# Voice.net
KiCad netlist of a schematic drawn in Altium Designer
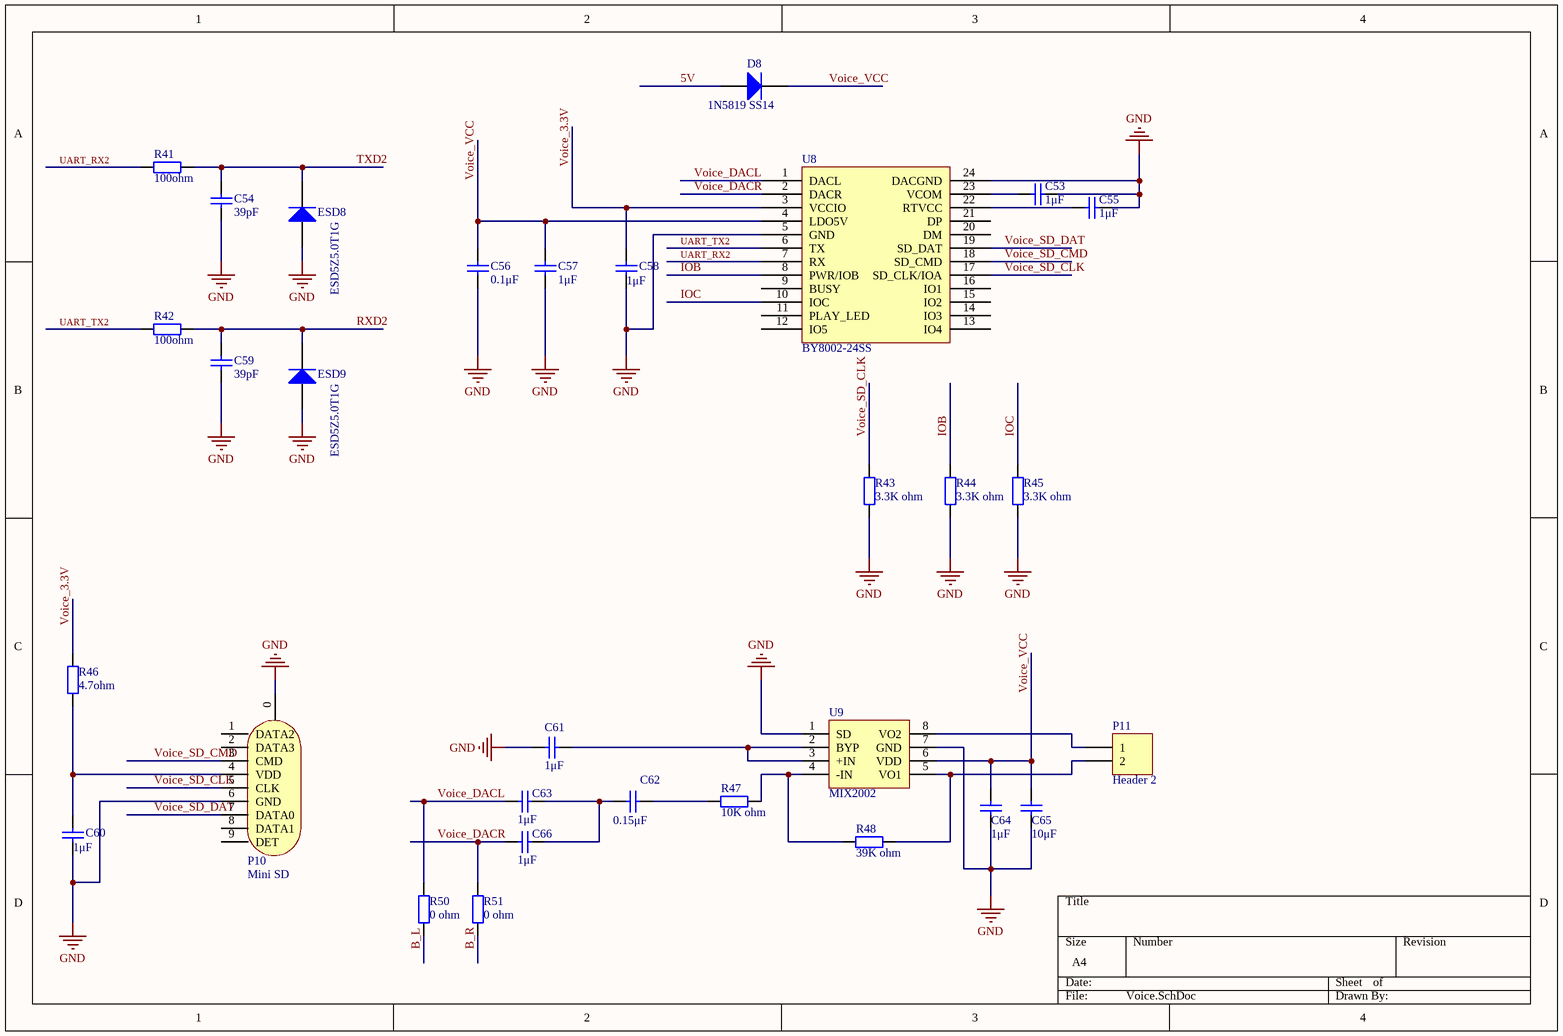
[diagram p0: Voice.SchDoc]

(export (version "E")
  (design (tool "Eeschema 10.0.6"))
  (components
    (comp (ref "C53")
      (value "1μF")
      (footprint "0603C")
      (description "1μF_50V,X5R,±10%")
      (libsource (lib "Yang_Lib") (part "Cap_1μF_50V_0603"))
    )
    (comp (ref "C54")
      (value "39pF")
      (footprint "0603C")
      (description "39pF_50V,C0G (EIA),±1%")
      (libsource (lib "Yang_Lib") (part "Cap_39pF_50V_0603"))
    )
    (comp (ref "C55")
      (value "1μF")
      (footprint "0603C")
      (description "1μF_50V,X5R,±10%")
      (libsource (lib "Yang_Lib") (part "Cap_1μF_50V_0603"))
    )
    (comp (ref "C56")
      (value "0.1μF")
      (footprint "0603C")
      (description "0.1μF_50V,X7R,±5%")
      (libsource (lib "Yang_Lib") (part "Cap_0.1μF_50V_0603"))
    )
    (comp (ref "C57")
      (value "1μF")
      (footprint "0603C")
      (description "1μF_50V,X5R,±10%")
      (libsource (lib "Yang_Lib") (part "Cap_1μF_50V_0603"))
    )
    (comp (ref "C58")
      (value "1μF")
      (footprint "0603C")
      (description "1μF_50V,X5R,±10%")
      (libsource (lib "Yang_Lib") (part "Cap_1μF_50V_0603"))
    )
    (comp (ref "C59")
      (value "39pF")
      (footprint "0603C")
      (description "39pF_50V,C0G (EIA),±1%")
      (libsource (lib "Yang_Lib") (part "Cap_39pF_50V_0603"))
    )
    (comp (ref "C60")
      (value "1μF")
      (footprint "0603C")
      (description "1μF_50V,X5R,±10%")
      (libsource (lib "Yang_Lib") (part "Cap_1μF_50V_0603"))
    )
    (comp (ref "C61")
      (value "1μF")
      (footprint "0603C")
      (description "1μF_50V,X5R,±10%")
      (libsource (lib "Yang_Lib") (part "Cap_1μF_50V_0603"))
    )
    (comp (ref "C62")
      (value "0.15μF")
      (footprint "0603C")
      (description "0.15μF_50V,X7R,±5%")
      (libsource (lib "Yang_Lib") (part "Cap_0.15μF_50V_0603"))
    )
    (comp (ref "C63")
      (value "1μF")
      (footprint "0603C")
      (description "1μF_50V,X5R,±10%")
      (libsource (lib "Yang_Lib") (part "Cap_1μF_50V_0603"))
    )
    (comp (ref "C64")
      (value "1μF")
      (footprint "0603C")
      (description "1μF_50V,X5R,±10%")
      (libsource (lib "Yang_Lib") (part "Cap_1μF_50V_0603"))
    )
    (comp (ref "C65")
      (value "10μF")
      (footprint "0603C")
      (description "10μF_35V,X5R,20%")
      (libsource (lib "Yang_Lib") (part "Cap_10μF_35V_0603"))
    )
    (comp (ref "C66")
      (value "1μF")
      (footprint "0603C")
      (description "1μF_50V,X5R,±10%")
      (libsource (lib "Yang_Lib") (part "Cap_1μF_50V_0603"))
    )
    (comp (ref "D8")
      (value "1N5819 SS14")
      (footprint "SMA-small")
      (libsource (lib "Yang_Lib") (part "1N5819 SS14_SMA"))
    )
    (comp (ref "ESD8")
      (value "ESD5Z5.0T1G")
      (footprint "SOD523")
      (libsource (lib "Yang_Lib") (part "ESD5Z5.0T1G_SOD523"))
    )
    (comp (ref "ESD9")
      (value "ESD5Z5.0T1G")
      (footprint "SOD523")
      (libsource (lib "Yang_Lib") (part "ESD5Z5.0T1G_SOD523"))
    )
    (comp (ref "P10") (value "Mini SD") (footprint "TF-tan") (libsource (lib "Yang_Lib") (part "Mini SD")))
    (comp (ref "P11")
      (value "Header 2")
      (footprint "HDR1X2")
      (description "Header, 2-Pin")
      (fields (field (name "PUBLISHER") "Altium Limited"))
      (libsource (lib "Miscellaneous Connectors") (part "Header 2"))
    )
    (comp (ref "R41")
      (value "100ohm")
      (footprint "0603R")
      (description "100 ohm_5%")
      (libsource (lib "Yang_Lib") (part "Res_100ohm_0603"))
    )
    (comp (ref "R42")
      (value "100ohm")
      (footprint "0603R")
      (description "100 ohm_5%")
      (libsource (lib "Yang_Lib") (part "Res_100ohm_0603"))
    )
    (comp (ref "R43")
      (value "3.3K ohm")
      (footprint "0603R")
      (description "3.3K ohm,1%")
      (libsource (lib "Yang_Lib") (part "Res_3.3K ohm_0603"))
    )
    (comp (ref "R44")
      (value "3.3K ohm")
      (footprint "0603R")
      (description "3.3K ohm,1%")
      (libsource (lib "Yang_Lib") (part "Res_3.3K ohm_0603"))
    )
    (comp (ref "R45")
      (value "3.3K ohm")
      (footprint "0603R")
      (description "3.3K ohm,1%")
      (libsource (lib "Yang_Lib") (part "Res_3.3K ohm_0603"))
    )
    (comp (ref "R46")
      (value "4.7ohm")
      (footprint "0603R")
      (description "4.7ohm,1%")
      (libsource (lib "Yang_Lib") (part "Res_4.7ohm_0603"))
    )
    (comp (ref "R47")
      (value "10K ohm")
      (footprint "0603R")
      (description "10K ohm,1%")
      (libsource (lib "Yang_Lib") (part "Res_10K ohm_0603"))
    )
    (comp (ref "R48")
      (value "39K ohm")
      (footprint "0603R")
      (description "39K ohm,1%")
      (libsource (lib "Yang_Lib") (part "Res_39K ohm_0603"))
    )
    (comp (ref "R50")
      (value "0 ohm")
      (footprint "0603R")
      (description "0 ohm,5%")
      (libsource (lib "Yang_Lib") (part "Res_0 ohm_0603"))
    )
    (comp (ref "R51")
      (value "0 ohm")
      (footprint "0603R")
      (description "0 ohm,5%")
      (libsource (lib "Yang_Lib") (part "Res_0 ohm_0603"))
    )
    (comp (ref "U8")
      (value "BY8002-24SS")
      (footprint "QSOP-24N")
      (libsource (lib "Yang_Lib") (part "BY8002-24SS"))
    )
    (comp (ref "U9")
      (value "MIX2002")
      (footprint "SOP8 - NO-HP")
      (libsource (lib "Yang_Lib") (part "MIX2002"))
    )
  )
  (nets
    (net (code "1") (name "/5V") (class "Default")
      (node (ref "D8") (pin "1") (pinfunction "A_1") (pintype "passive"))
    )
    (net (code "2") (name "/B_L") (class "Default")
      (node (ref "R50") (pin "1") (pinfunction "1_1") (pintype "passive"))
    )
    (net (code "3") (name "/B_R") (class "Default")
      (node (ref "R51") (pin "1") (pinfunction "1_1") (pintype "passive"))
    )
    (net (code "4") (name "/IOB") (class "Default")
      (node (ref "R44") (pin "2") (pinfunction "2_2") (pintype "passive"))
      (node (ref "U8") (pin "8") (pinfunction "PWR/IOB_8") (pintype "passive"))
    )
    (net (code "5") (name "/IOC") (class "Default")
      (node (ref "R45") (pin "2") (pinfunction "2_2") (pintype "passive"))
      (node (ref "U8") (pin "10") (pinfunction "IOC_10") (pintype "passive"))
    )
    (net (code "6") (name "/RXD2") (class "Default")
      (node (ref "C59") (pin "2") (pinfunction "2_2") (pintype "passive"))
      (node (ref "ESD9") (pin "2") (pinfunction "K_2") (pintype "passive"))
      (node (ref "R42") (pin "2") (pinfunction "2_2") (pintype "passive"))
    )
    (net (code "7") (name "/TXD2") (class "Default")
      (node (ref "C54") (pin "2") (pinfunction "2_2") (pintype "passive"))
      (node (ref "ESD8") (pin "2") (pinfunction "K_2") (pintype "passive"))
      (node (ref "R41") (pin "2") (pinfunction "2_2") (pintype "passive"))
    )
    (net (code "8") (name "/UART_RX2") (class "Default")
      (node (ref "R41") (pin "1") (pinfunction "1_1") (pintype "passive"))
      (node (ref "U8") (pin "7") (pinfunction "RX_7") (pintype "passive"))
    )
    (net (code "9") (name "/UART_TX2") (class "Default")
      (node (ref "R42") (pin "1") (pinfunction "1_1") (pintype "passive"))
      (node (ref "U8") (pin "6") (pinfunction "TX_6") (pintype "passive"))
    )
    (net (code "10") (name "/Voice_3.3V") (class "Default")
      (node (ref "C58") (pin "2") (pinfunction "2_2") (pintype "passive"))
      (node (ref "R46") (pin "2") (pinfunction "2_2") (pintype "passive"))
      (node (ref "U8") (pin "3") (pinfunction "VCCIO_3") (pintype "passive"))
    )
    (net (code "11") (name "/Voice_DACL") (class "Default")
      (node (ref "C63") (pin "1") (pinfunction "1_1") (pintype "passive"))
      (node (ref "R50") (pin "2") (pinfunction "2_2") (pintype "passive"))
      (node (ref "U8") (pin "1") (pinfunction "DACL_1") (pintype "passive"))
    )
    (net (code "12") (name "/Voice_DACR") (class "Default")
      (node (ref "C66") (pin "1") (pinfunction "1_1") (pintype "passive"))
      (node (ref "R51") (pin "2") (pinfunction "2_2") (pintype "passive"))
      (node (ref "U8") (pin "2") (pinfunction "DACR_2") (pintype "passive"))
    )
    (net (code "13") (name "/Voice_SD_CLK") (class "Default")
      (node (ref "P10") (pin "5") (pinfunction "CLK_5") (pintype "passive"))
      (node (ref "R43") (pin "2") (pinfunction "2_2") (pintype "passive"))
      (node (ref "U8") (pin "17") (pinfunction "SD_CLK/IOA_17") (pintype "passive"))
    )
    (net (code "14") (name "/Voice_SD_CMD") (class "Default")
      (node (ref "P10") (pin "3") (pinfunction "CMD_3") (pintype "passive"))
      (node (ref "U8") (pin "18") (pinfunction "SD_CMD_18") (pintype "passive"))
    )
    (net (code "15") (name "/Voice_SD_DAT") (class "Default")
      (node (ref "P10") (pin "7") (pinfunction "DATA0_7") (pintype "passive"))
      (node (ref "U8") (pin "19") (pinfunction "SD_DAT_19") (pintype "passive"))
    )
    (net (code "16") (name "/Voice_VCC") (class "Default")
      (node (ref "C56") (pin "2") (pinfunction "2_2") (pintype "passive"))
      (node (ref "C57") (pin "2") (pinfunction "2_2") (pintype "passive"))
      (node (ref "C64") (pin "2") (pinfunction "2_2") (pintype "passive"))
      (node (ref "C65") (pin "2") (pinfunction "2_2") (pintype "passive"))
      (node (ref "D8") (pin "2") (pinfunction "K_2") (pintype "passive"))
      (node (ref "U8") (pin "4") (pinfunction "LDO5V_4") (pintype "passive"))
      (node (ref "U9") (pin "6") (pinfunction "VDD_6") (pintype "passive"))
    )
    (net (code "17") (name "GND") (class "Default")
      (node (ref "C53") (pin "1") (pinfunction "1_1") (pintype "passive"))
      (node (ref "C54") (pin "1") (pinfunction "1_1") (pintype "passive"))
      (node (ref "C55") (pin "1") (pinfunction "1_1") (pintype "passive"))
      (node (ref "C56") (pin "1") (pinfunction "1_1") (pintype "passive"))
      (node (ref "C57") (pin "1") (pinfunction "1_1") (pintype "passive"))
      (node (ref "C58") (pin "1") (pinfunction "1_1") (pintype "passive"))
      (node (ref "C59") (pin "1") (pinfunction "1_1") (pintype "passive"))
      (node (ref "C60") (pin "1") (pinfunction "1_1") (pintype "passive"))
      (node (ref "C61") (pin "1") (pinfunction "1_1") (pintype "passive"))
      (node (ref "C64") (pin "1") (pinfunction "1_1") (pintype "passive"))
      (node (ref "C65") (pin "1") (pinfunction "1_1") (pintype "passive"))
      (node (ref "ESD8") (pin "1") (pinfunction "A_1") (pintype "passive"))
      (node (ref "ESD9") (pin "1") (pinfunction "A_1") (pintype "passive"))
      (node (ref "P10") (pin "0") (pinfunction "0_0") (pintype "passive"))
      (node (ref "P10") (pin "6") (pinfunction "GND_6") (pintype "passive"))
      (node (ref "R43") (pin "1") (pinfunction "1_1") (pintype "passive"))
      (node (ref "R44") (pin "1") (pinfunction "1_1") (pintype "passive"))
      (node (ref "R45") (pin "1") (pinfunction "1_1") (pintype "passive"))
      (node (ref "U8") (pin "24") (pinfunction "DACGND_24") (pintype "passive"))
      (node (ref "U8") (pin "5") (pinfunction "GND_5") (pintype "passive"))
      (node (ref "U9") (pin "1") (pinfunction "SD_1") (pintype "passive"))
      (node (ref "U9") (pin "7") (pinfunction "GND_7") (pintype "passive"))
    )
    (net (code "18") (name "Net-(C62-Pad1)") (class "Default")
      (node (ref "C62") (pin "1") (pinfunction "1_1") (pintype "passive"))
      (node (ref "C63") (pin "2") (pinfunction "2_2") (pintype "passive"))
      (node (ref "C66") (pin "2") (pinfunction "2_2") (pintype "passive"))
    )
    (net (code "19") (name "Net-(C62-Pad2)") (class "Default")
      (node (ref "C62") (pin "2") (pinfunction "2_2") (pintype "passive"))
      (node (ref "R47") (pin "1") (pinfunction "1_1") (pintype "passive"))
    )
    (net (code "20") (name "Net-(P10-VDD)") (class "Default")
      (node (ref "C60") (pin "2") (pinfunction "2_2") (pintype "passive"))
      (node (ref "P10") (pin "4") (pinfunction "VDD_4") (pintype "passive"))
      (node (ref "R46") (pin "1") (pinfunction "1_1") (pintype "passive"))
    )
    (net (code "21") (name "Net-(U8-RTVCC)") (class "Default")
      (node (ref "C55") (pin "2") (pinfunction "2_2") (pintype "passive"))
      (node (ref "U8") (pin "22") (pinfunction "RTVCC_22") (pintype "passive"))
    )
    (net (code "22") (name "Net-(U8-VCOM)") (class "Default")
      (node (ref "C53") (pin "2") (pinfunction "2_2") (pintype "passive"))
      (node (ref "U8") (pin "23") (pinfunction "VCOM_23") (pintype "passive"))
    )
    (net (code "23") (name "Net-(U9-+IN)") (class "Default")
      (node (ref "C61") (pin "2") (pinfunction "2_2") (pintype "passive"))
      (node (ref "U9") (pin "2") (pinfunction "BYP_2") (pintype "passive"))
      (node (ref "U9") (pin "3") (pinfunction "+IN_3") (pintype "passive"))
    )
    (net (code "24") (name "Net-(U9--IN)") (class "Default")
      (node (ref "R47") (pin "2") (pinfunction "2_2") (pintype "passive"))
      (node (ref "R48") (pin "1") (pinfunction "1_1") (pintype "passive"))
      (node (ref "U9") (pin "4") (pinfunction "-IN_4") (pintype "passive"))
    )
    (net (code "25") (name "Net-(U9-VO1)") (class "Default")
      (node (ref "P11") (pin "2") (pinfunction "2_2") (pintype "passive"))
      (node (ref "R48") (pin "2") (pinfunction "2_2") (pintype "passive"))
      (node (ref "U9") (pin "5") (pinfunction "VO1_5") (pintype "passive"))
    )
    (net (code "26") (name "Net-(U9-VO2)") (class "Default")
      (node (ref "P11") (pin "1") (pinfunction "1_1") (pintype "passive"))
      (node (ref "U9") (pin "8") (pinfunction "VO2_8") (pintype "passive"))
    )
    (net (code "27") (name "unconnected-(P10-DATA1-Pad8)") (class "Default")
      (node (ref "P10") (pin "8") (pinfunction "DATA1_8") (pintype "passive"))
    )
    (net (code "28") (name "unconnected-(P10-DATA2-Pad1)") (class "Default")
      (node (ref "P10") (pin "1") (pinfunction "DATA2_1") (pintype "passive"))
    )
    (net (code "29") (name "unconnected-(P10-DATA3-Pad2)") (class "Default")
      (node (ref "P10") (pin "2") (pinfunction "DATA3_2") (pintype "passive"))
    )
    (net (code "30") (name "unconnected-(P10-DET-Pad9)") (class "Default")
      (node (ref "P10") (pin "9") (pinfunction "DET_9") (pintype "passive"))
    )
    (net (code "31") (name "unconnected-(U8-BUSY-Pad9)") (class "Default")
      (node (ref "U8") (pin "9") (pinfunction "BUSY_9") (pintype "passive"))
    )
    (net (code "32") (name "unconnected-(U8-DM-Pad20)") (class "Default")
      (node (ref "U8") (pin "20") (pinfunction "DM_20") (pintype "passive"))
    )
    (net (code "33") (name "unconnected-(U8-DP-Pad21)") (class "Default")
      (node (ref "U8") (pin "21") (pinfunction "DP_21") (pintype "passive"))
    )
    (net (code "34") (name "unconnected-(U8-IO1-Pad16)") (class "Default")
      (node (ref "U8") (pin "16") (pinfunction "IO1_16") (pintype "passive"))
    )
    (net (code "35") (name "unconnected-(U8-IO2-Pad15)") (class "Default")
      (node (ref "U8") (pin "15") (pinfunction "IO2_15") (pintype "passive"))
    )
    (net (code "36") (name "unconnected-(U8-IO3-Pad14)") (class "Default")
      (node (ref "U8") (pin "14") (pinfunction "IO3_14") (pintype "passive"))
    )
    (net (code "37") (name "unconnected-(U8-IO4-Pad13)") (class "Default")
      (node (ref "U8") (pin "13") (pinfunction "IO4_13") (pintype "passive"))
    )
    (net (code "38") (name "unconnected-(U8-IO5-Pad12)") (class "Default")
      (node (ref "U8") (pin "12") (pinfunction "IO5_12") (pintype "passive"))
    )
    (net (code "39") (name "unconnected-(U8-PLAY_LED-Pad11)") (class "Default")
      (node (ref "U8") (pin "11") (pinfunction "PLAY_LED_11") (pintype "passive"))
    )
  )
)
